# demeter_v22.net
KiCad netlist of a schematic drawn in EAGLE
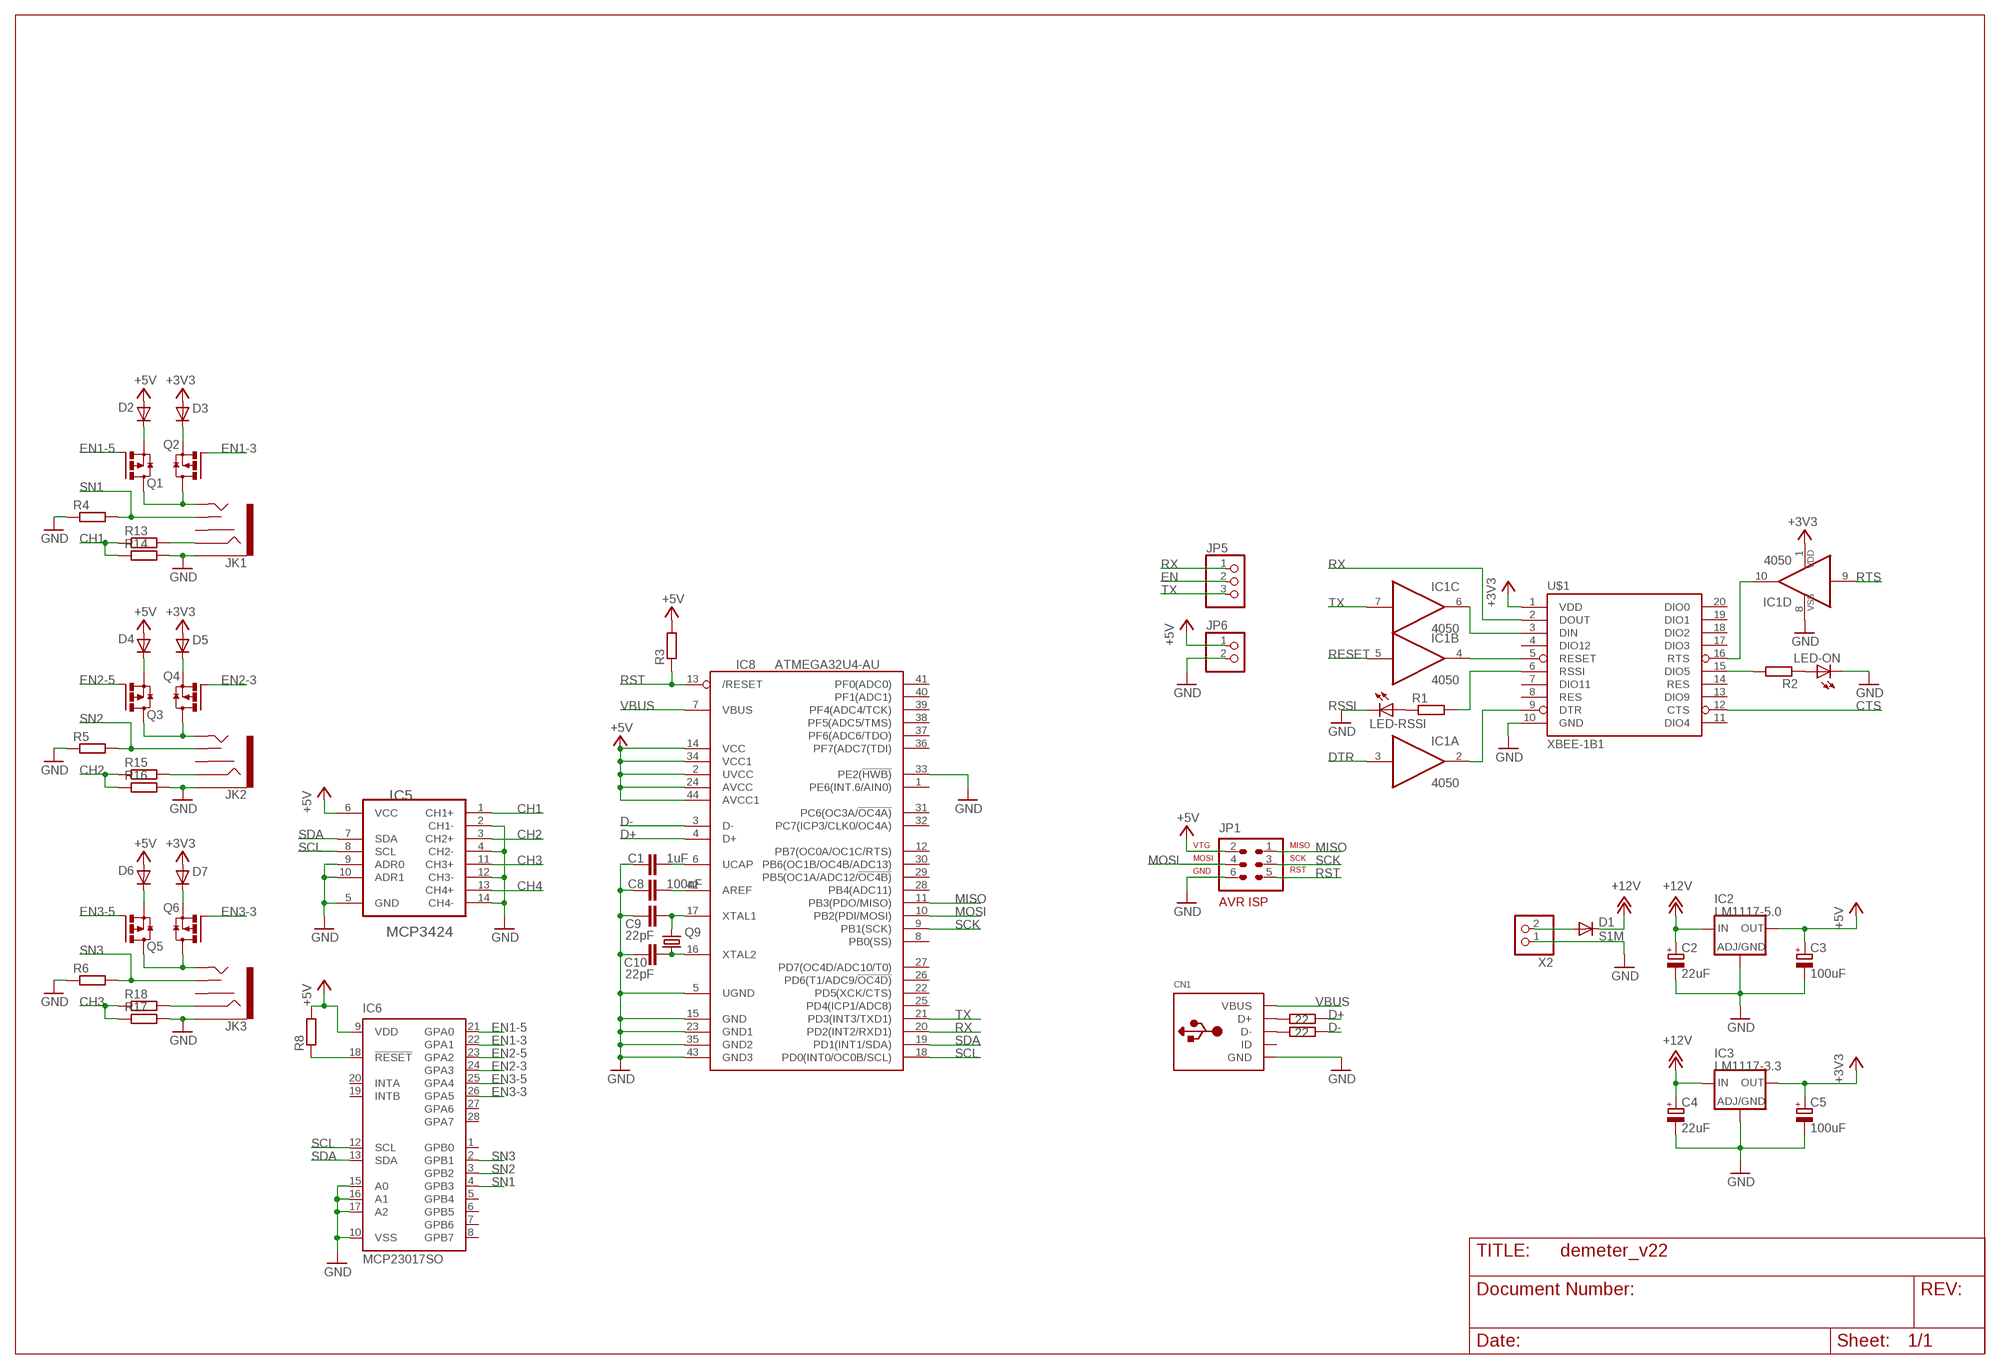
[diagram p0: schematic, sheet 1]

(export (version "E")
  (design (tool "Eeschema 10.0.6"))
  (components
    (comp (ref "C1")
      (value "1uF")
      (footprint "eagle-import:C0805K")
      (libsource (lib "eagle-import") (part "C-EUC0805K"))
    )
    (comp (ref "C2")
      (value "22uF")
      (footprint "eagle-import:PANASONIC_D")
      (libsource (lib "eagle-import") (part "CPOL-EUPD"))
    )
    (comp (ref "C3")
      (value "100uF")
      (footprint "eagle-import:PANASONIC_D")
      (libsource (lib "eagle-import") (part "CPOL-EUPD"))
    )
    (comp (ref "C4")
      (value "22uF")
      (footprint "eagle-import:PANASONIC_D")
      (libsource (lib "eagle-import") (part "CPOL-EUPD"))
    )
    (comp (ref "C5")
      (value "100uF")
      (footprint "eagle-import:PANASONIC_D")
      (libsource (lib "eagle-import") (part "CPOL-EUPD"))
    )
    (comp (ref "C8")
      (value "100nF")
      (footprint "eagle-import:C0805K")
      (libsource (lib "eagle-import") (part "C-EUC0805K"))
    )
    (comp (ref "C9")
      (value "22pF")
      (footprint "eagle-import:C0805K")
      (libsource (lib "eagle-import") (part "C-EUC0805K"))
    )
    (comp (ref "C10")
      (value "22pF")
      (footprint "eagle-import:C0805K")
      (libsource (lib "eagle-import") (part "C-EUC0805K"))
    )
    (comp (ref "CN1")
      (value "USBMINIB")
      (footprint "eagle-import:USB-MINIB")
      (libsource (lib "eagle-import") (part "USBMINIB"))
    )
    (comp (ref "D1")
      (value "S1M")
      (footprint "eagle-import:DO-214AC")
      (libsource (lib "eagle-import") (part "S1M"))
    )
    (comp (ref "D2")
      (value "MBR0520")
      (footprint "eagle-import:SOD123")
      (libsource (lib "eagle-import") (part "MBR0520"))
    )
    (comp (ref "D3")
      (value "MBR0520")
      (footprint "eagle-import:SOD123")
      (libsource (lib "eagle-import") (part "MBR0520"))
    )
    (comp (ref "D4")
      (value "MBR0520")
      (footprint "eagle-import:SOD123")
      (libsource (lib "eagle-import") (part "MBR0520"))
    )
    (comp (ref "D5")
      (value "MBR0520")
      (footprint "eagle-import:SOD123")
      (libsource (lib "eagle-import") (part "MBR0520"))
    )
    (comp (ref "D6")
      (value "MBR0520")
      (footprint "eagle-import:SOD123")
      (libsource (lib "eagle-import") (part "MBR0520"))
    )
    (comp (ref "D7")
      (value "MBR0520")
      (footprint "eagle-import:SOD123")
      (libsource (lib "eagle-import") (part "MBR0520"))
    )
    (comp (ref "IC1")
      (value "4050")
      (footprint "eagle-import:SO16")
      (libsource (lib "eagle-import") (part "4050D"))
    )
    (comp (ref "IC2")
      (value "LM1117-5.0")
      (footprint "eagle-import:DPACK")
      (libsource (lib "eagle-import") (part "LM1117DT"))
    )
    (comp (ref "IC3")
      (value "LM1117-3.3")
      (footprint "eagle-import:DPACK")
      (libsource (lib "eagle-import") (part "LM1117DT"))
    )
    (comp (ref "IC5")
      (value "MCP3424")
      (footprint "eagle-import:SO14")
      (fields (field (name "MPN") "MCP3424-E/SL"))
      (libsource (lib "eagle-import") (part "MCP3424"))
    )
    (comp (ref "IC6")
      (value "MCP23017SO")
      (footprint "eagle-import:SO28W")
      (fields (field (name "MF") "MICROCHIP") (field (name "MPN") "MCP23017-E/SO"))
      (libsource (lib "eagle-import") (part "MCP23017SO"))
    )
    (comp (ref "IC8")
      (value "ATMEGA32U4-AU")
      (footprint "eagle-import:TQFP44")
      (libsource (lib "eagle-import") (part "ATMEGA32U4-AU"))
    )
    (comp (ref "JK1")
      (value "AUDIO-JACK2PTH")
      (footprint "eagle-import:AUDIO-JACK")
      (libsource (lib "eagle-import") (part "AUDIO-JACK2PTH"))
    )
    (comp (ref "JK2")
      (value "AUDIO-JACK2PTH")
      (footprint "eagle-import:AUDIO-JACK")
      (libsource (lib "eagle-import") (part "AUDIO-JACK2PTH"))
    )
    (comp (ref "JK3")
      (value "AUDIO-JACK2PTH")
      (footprint "eagle-import:AUDIO-JACK")
      (libsource (lib "eagle-import") (part "AUDIO-JACK2PTH"))
    )
    (comp (ref "JP1")
      (value "AVR-ISP-6")
      (footprint "eagle-import:AVR-ISP-6")
      (libsource (lib "eagle-import") (part "AVR-ISP-6"))
    )
    (comp (ref "JP5")
      (value "PINHD-1X3180")
      (footprint "eagle-import:1X03")
      (libsource (lib "eagle-import") (part "PINHD-1X3180"))
    )
    (comp (ref "JP6")
      (value "PINHD-1X2")
      (footprint "eagle-import:1X02")
      (libsource (lib "eagle-import") (part "PINHD-1X2"))
    )
    (comp (ref "LED-ON")
      (value "LED0805")
      (footprint "eagle-import:CHIP-LED0805")
      (libsource (lib "eagle-import") (part "LED0805"))
    )
    (comp (ref "LED-RSSI")
      (value "LED0805")
      (footprint "eagle-import:CHIP-LED0805")
      (libsource (lib "eagle-import") (part "LED0805"))
    )
    (comp (ref "Q1")
      (value "IRLML6402")
      (footprint "eagle-import:SOT23")
      (libsource (lib "eagle-import") (part "IRLML6402"))
    )
    (comp (ref "Q2")
      (value "IRLML6402")
      (footprint "eagle-import:SOT23")
      (libsource (lib "eagle-import") (part "IRLML6402"))
    )
    (comp (ref "Q3")
      (value "IRLML6402")
      (footprint "eagle-import:SOT23")
      (libsource (lib "eagle-import") (part "IRLML6402"))
    )
    (comp (ref "Q4")
      (value "IRLML6402")
      (footprint "eagle-import:SOT23")
      (libsource (lib "eagle-import") (part "IRLML6402"))
    )
    (comp (ref "Q5")
      (value "IRLML6402")
      (footprint "eagle-import:SOT23")
      (libsource (lib "eagle-import") (part "IRLML6402"))
    )
    (comp (ref "Q6")
      (value "IRLML6402")
      (footprint "eagle-import:SOT23")
      (libsource (lib "eagle-import") (part "IRLML6402"))
    )
    (comp (ref "Q9")
      (value "CRYSTALHC49UP")
      (footprint "eagle-import:HC49UP")
      (libsource (lib "eagle-import") (part "CRYSTALHC49UP"))
    )
    (comp (ref "R1")
      (value "R-EU_R0805")
      (footprint "eagle-import:R0805")
      (libsource (lib "eagle-import") (part "R-EU_R0805"))
    )
    (comp (ref "R2")
      (value "R-EU_R0805")
      (footprint "eagle-import:R0805")
      (libsource (lib "eagle-import") (part "R-EU_R0805"))
    )
    (comp (ref "R3")
      (value "R-EU_R0805")
      (footprint "eagle-import:R0805")
      (libsource (lib "eagle-import") (part "R-EU_R0805"))
    )
    (comp (ref "R4")
      (value "R-EU_R0805")
      (footprint "eagle-import:R0805")
      (libsource (lib "eagle-import") (part "R-EU_R0805"))
    )
    (comp (ref "R5")
      (value "R-EU_R0805")
      (footprint "eagle-import:R0805")
      (libsource (lib "eagle-import") (part "R-EU_R0805"))
    )
    (comp (ref "R6")
      (value "R-EU_R0805")
      (footprint "eagle-import:R0805")
      (libsource (lib "eagle-import") (part "R-EU_R0805"))
    )
    (comp (ref "R8")
      (value "R-EU_R0805")
      (footprint "eagle-import:R0805")
      (libsource (lib "eagle-import") (part "R-EU_R0805"))
    )
    (comp (ref "R9")
      (value "22")
      (footprint "eagle-import:R0805")
      (libsource (lib "eagle-import") (part "R-EU_R0805"))
    )
    (comp (ref "R10")
      (value "22")
      (footprint "eagle-import:R0805")
      (libsource (lib "eagle-import") (part "R-EU_R0805"))
    )
    (comp (ref "R13")
      (value "R-EU_R0805")
      (footprint "eagle-import:R0805")
      (libsource (lib "eagle-import") (part "R-EU_R0805"))
    )
    (comp (ref "R14")
      (value "R-EU_R0805")
      (footprint "eagle-import:R0805")
      (libsource (lib "eagle-import") (part "R-EU_R0805"))
    )
    (comp (ref "R15")
      (value "R-EU_R0805")
      (footprint "eagle-import:R0805")
      (libsource (lib "eagle-import") (part "R-EU_R0805"))
    )
    (comp (ref "R16")
      (value "R-EU_R0805")
      (footprint "eagle-import:R0805")
      (libsource (lib "eagle-import") (part "R-EU_R0805"))
    )
    (comp (ref "R17")
      (value "R-EU_R0805")
      (footprint "eagle-import:R0805")
      (libsource (lib "eagle-import") (part "R-EU_R0805"))
    )
    (comp (ref "R18")
      (value "R-EU_R0805")
      (footprint "eagle-import:R0805")
      (libsource (lib "eagle-import") (part "R-EU_R0805"))
    )
    (comp (ref "U$1")
      (value "XBEE-1B1")
      (footprint "eagle-import:XBEE-1")
      (libsource (lib "eagle-import") (part "XBEE-1B1"))
    )
    (comp (ref "X2")
      (value "W237-102")
      (footprint "eagle-import:W237-102")
      (libsource (lib "eagle-import") (part "W237-102"))
    )
  )
  (nets
    (net (code "1") (name "+3V3") (class "Default")
      (node (ref "C5") (pin "+") (pinfunction "+_+") (pintype "passive"))
      (node (ref "D3") (pin "A") (pinfunction "A_A") (pintype "passive"))
      (node (ref "D5") (pin "A") (pinfunction "A_A") (pintype "passive"))
      (node (ref "D7") (pin "A") (pinfunction "A_A") (pintype "passive"))
      (node (ref "IC1") (pin "1") (pinfunction "VDD_1") (pintype "power_in"))
      (node (ref "IC3") (pin "4") (pinfunction "OUT_4") (pintype "passive"))
      (node (ref "U$1") (pin "1") (pinfunction "VDD_1") (pintype "power_in"))
    )
    (net (code "2") (name "+5V") (class "Default")
      (node (ref "C3") (pin "+") (pinfunction "+_+") (pintype "passive"))
      (node (ref "D2") (pin "A") (pinfunction "A_A") (pintype "passive"))
      (node (ref "D4") (pin "A") (pinfunction "A_A") (pintype "passive"))
      (node (ref "D6") (pin "A") (pinfunction "A_A") (pintype "passive"))
      (node (ref "IC2") (pin "4") (pinfunction "OUT_4") (pintype "passive"))
      (node (ref "IC5") (pin "6") (pinfunction "VCC_6") (pintype "power_in"))
      (node (ref "IC6") (pin "9") (pinfunction "VDD_9") (pintype "power_in"))
      (node (ref "IC8") (pin "14") (pinfunction "VCC_14") (pintype "bidirectional"))
      (node (ref "IC8") (pin "2") (pinfunction "UVCC_2") (pintype "bidirectional"))
      (node (ref "IC8") (pin "24") (pinfunction "AVCC_24") (pintype "bidirectional"))
      (node (ref "IC8") (pin "34") (pinfunction "VCC1_34") (pintype "bidirectional"))
      (node (ref "IC8") (pin "44") (pinfunction "AVCC1_44") (pintype "bidirectional"))
      (node (ref "JP1") (pin "2") (pinfunction "VTG_2") (pintype "passive"))
      (node (ref "JP6") (pin "1") (pinfunction "1_1") (pintype "passive"))
      (node (ref "R3") (pin "2") (pinfunction "2_2") (pintype "passive"))
      (node (ref "R8") (pin "2") (pinfunction "2_2") (pintype "passive"))
    )
    (net (code "3") (name "+12V") (class "Default")
      (node (ref "C2") (pin "+") (pinfunction "+_+") (pintype "passive"))
      (node (ref "C4") (pin "+") (pinfunction "+_+") (pintype "passive"))
      (node (ref "D1") (pin "C") (pinfunction "C_C") (pintype "passive"))
      (node (ref "IC2") (pin "3") (pinfunction "IN_3") (pintype "input"))
      (node (ref "IC3") (pin "3") (pinfunction "IN_3") (pintype "input"))
    )
    (net (code "4") (name "/CH1") (class "Default")
      (node (ref "IC5") (pin "1") (pinfunction "CH1+_1") (pintype "input"))
      (node (ref "R13") (pin "1") (pinfunction "1_1") (pintype "passive"))
      (node (ref "R14") (pin "1") (pinfunction "1_1") (pintype "passive"))
    )
    (net (code "5") (name "/CH2") (class "Default")
      (node (ref "IC5") (pin "3") (pinfunction "CH2+_3") (pintype "input"))
      (node (ref "R15") (pin "1") (pinfunction "1_1") (pintype "passive"))
      (node (ref "R16") (pin "1") (pinfunction "1_1") (pintype "passive"))
    )
    (net (code "6") (name "/CH3") (class "Default")
      (node (ref "IC5") (pin "11") (pinfunction "CH3+_11") (pintype "input"))
      (node (ref "R17") (pin "1") (pinfunction "1_1") (pintype "passive"))
      (node (ref "R18") (pin "1") (pinfunction "1_1") (pintype "passive"))
    )
    (net (code "7") (name "/CH4") (class "Default")
      (node (ref "IC5") (pin "13") (pinfunction "CH4+_13") (pintype "input"))
    )
    (net (code "8") (name "/CTS") (class "Default")
      (node (ref "U$1") (pin "12") (pinfunction "CTS_12") (pintype "output"))
    )
    (net (code "9") (name "/D+") (class "Default")
      (node (ref "IC8") (pin "4") (pinfunction "D+_4") (pintype "bidirectional"))
      (node (ref "R9") (pin "1") (pinfunction "1_1") (pintype "passive"))
    )
    (net (code "10") (name "/D-") (class "Default")
      (node (ref "IC8") (pin "3") (pinfunction "D-_3") (pintype "bidirectional"))
      (node (ref "R10") (pin "1") (pinfunction "1_1") (pintype "passive"))
    )
    (net (code "11") (name "/DTR") (class "Default")
      (node (ref "IC1") (pin "3") (pinfunction "I_3") (pintype "input"))
    )
    (net (code "12") (name "/EN") (class "Default")
      (node (ref "JP5") (pin "2") (pinfunction "2_2") (pintype "passive"))
    )
    (net (code "13") (name "/EN1-3") (class "Default")
      (node (ref "IC6") (pin "22") (pinfunction "GPA1_22") (pintype "bidirectional"))
      (node (ref "Q2") (pin "1") (pinfunction "G_1") (pintype "passive"))
    )
    (net (code "14") (name "/EN1-5") (class "Default")
      (node (ref "IC6") (pin "21") (pinfunction "GPA0_21") (pintype "bidirectional"))
      (node (ref "Q1") (pin "1") (pinfunction "G_1") (pintype "passive"))
    )
    (net (code "15") (name "/EN2-3") (class "Default")
      (node (ref "IC6") (pin "24") (pinfunction "GPA3_24") (pintype "bidirectional"))
      (node (ref "Q4") (pin "1") (pinfunction "G_1") (pintype "passive"))
    )
    (net (code "16") (name "/EN2-5") (class "Default")
      (node (ref "IC6") (pin "23") (pinfunction "GPA2_23") (pintype "bidirectional"))
      (node (ref "Q3") (pin "1") (pinfunction "G_1") (pintype "passive"))
    )
    (net (code "17") (name "/EN3-3") (class "Default")
      (node (ref "IC6") (pin "26") (pinfunction "GPA5_26") (pintype "bidirectional"))
      (node (ref "Q6") (pin "1") (pinfunction "G_1") (pintype "passive"))
    )
    (net (code "18") (name "/EN3-5") (class "Default")
      (node (ref "IC6") (pin "25") (pinfunction "GPA4_25") (pintype "bidirectional"))
      (node (ref "Q5") (pin "1") (pinfunction "G_1") (pintype "passive"))
    )
    (net (code "19") (name "/MISO") (class "Default")
      (node (ref "IC8") (pin "11") (pinfunction "PB3(PDO/MISO)_11") (pintype "bidirectional"))
      (node (ref "JP1") (pin "1") (pinfunction "MISO_1") (pintype "passive"))
    )
    (net (code "20") (name "/MOSI") (class "Default")
      (node (ref "IC8") (pin "10") (pinfunction "PB2(PDI/MOSI)_10") (pintype "bidirectional"))
      (node (ref "JP1") (pin "4") (pinfunction "MOSI_4") (pintype "passive"))
    )
    (net (code "21") (name "/RESET") (class "Default")
      (node (ref "IC1") (pin "5") (pinfunction "I_5") (pintype "input"))
    )
    (net (code "22") (name "/RSSI") (class "Default")
      (node (ref "R1") (pin "2") (pinfunction "2_2") (pintype "passive"))
      (node (ref "U$1") (pin "6") (pinfunction "RSSI_6") (pintype "bidirectional"))
    )
    (net (code "23") (name "/RST") (class "Default")
      (node (ref "IC8") (pin "13") (pinfunction "/RESET_13") (pintype "bidirectional"))
      (node (ref "JP1") (pin "5") (pinfunction "RST_5") (pintype "passive"))
      (node (ref "R3") (pin "1") (pinfunction "1_1") (pintype "passive"))
    )
    (net (code "24") (name "/RTS") (class "Default")
      (node (ref "IC1") (pin "9") (pinfunction "I_9") (pintype "input"))
    )
    (net (code "25") (name "/RX") (class "Default")
      (node (ref "IC8") (pin "20") (pinfunction "PD2(INT2/RXD1)_20") (pintype "bidirectional"))
      (node (ref "JP5") (pin "1") (pinfunction "1_1") (pintype "passive"))
      (node (ref "U$1") (pin "2") (pinfunction "DOUT_2") (pintype "output"))
    )
    (net (code "26") (name "/SCK") (class "Default")
      (node (ref "IC8") (pin "9") (pinfunction "PB1(SCK)_9") (pintype "bidirectional"))
      (node (ref "JP1") (pin "3") (pinfunction "SCK_3") (pintype "passive"))
    )
    (net (code "27") (name "/SCL") (class "Default")
      (node (ref "IC5") (pin "8") (pinfunction "SCL_8") (pintype "input"))
      (node (ref "IC6") (pin "12") (pinfunction "SCL_12") (pintype "input"))
      (node (ref "IC8") (pin "18") (pinfunction "PD0(INT0/OC0B/SCL)_18") (pintype "bidirectional"))
    )
    (net (code "28") (name "/SDA") (class "Default")
      (node (ref "IC5") (pin "7") (pinfunction "SDA_7") (pintype "bidirectional"))
      (node (ref "IC6") (pin "13") (pinfunction "SDA_13") (pintype "bidirectional"))
      (node (ref "IC8") (pin "19") (pinfunction "PD1(INT1/SDA)_19") (pintype "bidirectional"))
    )
    (net (code "29") (name "/SN1") (class "Default")
      (node (ref "IC6") (pin "4") (pinfunction "GPB3_4") (pintype "bidirectional"))
      (node (ref "JK1") (pin "TSH") (pinfunction "TSH_TSH") (pintype "bidirectional"))
      (node (ref "R4") (pin "2") (pinfunction "2_2") (pintype "passive"))
    )
    (net (code "30") (name "/SN2") (class "Default")
      (node (ref "IC6") (pin "3") (pinfunction "GPB2_3") (pintype "bidirectional"))
      (node (ref "JK2") (pin "TSH") (pinfunction "TSH_TSH") (pintype "bidirectional"))
      (node (ref "R5") (pin "2") (pinfunction "2_2") (pintype "passive"))
    )
    (net (code "31") (name "/SN3") (class "Default")
      (node (ref "IC6") (pin "2") (pinfunction "GPB1_2") (pintype "bidirectional"))
      (node (ref "JK3") (pin "TSH") (pinfunction "TSH_TSH") (pintype "bidirectional"))
      (node (ref "R6") (pin "2") (pinfunction "2_2") (pintype "passive"))
    )
    (net (code "32") (name "/TX") (class "Default")
      (node (ref "IC1") (pin "7") (pinfunction "I_7") (pintype "input"))
      (node (ref "IC8") (pin "21") (pinfunction "PD3(INT3/TXD1)_21") (pintype "bidirectional"))
      (node (ref "JP5") (pin "3") (pinfunction "3_3") (pintype "passive"))
    )
    (net (code "33") (name "/VBUS") (class "Default")
      (node (ref "CN1") (pin "VBUS") (pinfunction "VBUS_VBUS") (pintype "power_in"))
      (node (ref "IC8") (pin "7") (pinfunction "VBUS_7") (pintype "bidirectional"))
    )
    (net (code "34") (name "GND") (class "Default")
      (node (ref "C1") (pin "2") (pinfunction "2_2") (pintype "passive"))
      (node (ref "C10") (pin "2") (pinfunction "2_2") (pintype "passive"))
      (node (ref "C2") (pin "-") (pinfunction "-_-") (pintype "passive"))
      (node (ref "C3") (pin "-") (pinfunction "-_-") (pintype "passive"))
      (node (ref "C4") (pin "-") (pinfunction "-_-") (pintype "passive"))
      (node (ref "C5") (pin "-") (pinfunction "-_-") (pintype "passive"))
      (node (ref "C8") (pin "2") (pinfunction "2_2") (pintype "passive"))
      (node (ref "C9") (pin "2") (pinfunction "2_2") (pintype "passive"))
      (node (ref "CN1") (pin "GND") (pinfunction "GND_GND") (pintype "power_in"))
      (node (ref "IC1") (pin "8") (pinfunction "VSS_8") (pintype "power_in"))
      (node (ref "IC2") (pin "1") (pinfunction "ADJ_1") (pintype "input"))
      (node (ref "IC3") (pin "1") (pinfunction "ADJ_1") (pintype "input"))
      (node (ref "IC5") (pin "10") (pinfunction "ADR1_10") (pintype "input"))
      (node (ref "IC5") (pin "12") (pinfunction "CH3-_12") (pintype "input"))
      (node (ref "IC5") (pin "14") (pinfunction "CH4-_14") (pintype "input"))
      (node (ref "IC5") (pin "2") (pinfunction "CH1-_2") (pintype "input"))
      (node (ref "IC5") (pin "4") (pinfunction "CH2-_4") (pintype "input"))
      (node (ref "IC5") (pin "5") (pinfunction "GND_5") (pintype "power_in"))
      (node (ref "IC5") (pin "9") (pinfunction "ADR0_9") (pintype "input"))
      (node (ref "IC6") (pin "10") (pinfunction "VSS_10") (pintype "power_in"))
      (node (ref "IC6") (pin "15") (pinfunction "A0_15") (pintype "input"))
      (node (ref "IC6") (pin "16") (pinfunction "A1_16") (pintype "input"))
      (node (ref "IC6") (pin "17") (pinfunction "A2_17") (pintype "input"))
      (node (ref "IC8") (pin "15") (pinfunction "GND_15") (pintype "bidirectional"))
      (node (ref "IC8") (pin "23") (pinfunction "GND1_23") (pintype "bidirectional"))
      (node (ref "IC8") (pin "33") (pinfunction "PE2(~{HWB})_33") (pintype "bidirectional"))
      (node (ref "IC8") (pin "35") (pinfunction "GND2_35") (pintype "bidirectional"))
      (node (ref "IC8") (pin "43") (pinfunction "GND3_43") (pintype "bidirectional"))
      (node (ref "IC8") (pin "5") (pinfunction "UGND_5") (pintype "bidirectional"))
      (node (ref "JK1") (pin "SLEEVE") (pinfunction "SLEEVE_SLEEVE") (pintype "bidirectional"))
      (node (ref "JK2") (pin "SLEEVE") (pinfunction "SLEEVE_SLEEVE") (pintype "bidirectional"))
      (node (ref "JK3") (pin "SLEEVE") (pinfunction "SLEEVE_SLEEVE") (pintype "bidirectional"))
      (node (ref "JP1") (pin "6") (pinfunction "GND_6") (pintype "passive"))
      (node (ref "JP6") (pin "2") (pinfunction "2_2") (pintype "passive"))
      (node (ref "LED-ON") (pin "C") (pinfunction "C_C") (pintype "passive"))
      (node (ref "LED-RSSI") (pin "C") (pinfunction "C_C") (pintype "passive"))
      (node (ref "R14") (pin "2") (pinfunction "2_2") (pintype "passive"))
      (node (ref "R16") (pin "2") (pinfunction "2_2") (pintype "passive"))
      (node (ref "R17") (pin "2") (pinfunction "2_2") (pintype "passive"))
      (node (ref "R4") (pin "1") (pinfunction "1_1") (pintype "passive"))
      (node (ref "R5") (pin "1") (pinfunction "1_1") (pintype "passive"))
      (node (ref "R6") (pin "1") (pinfunction "1_1") (pintype "passive"))
      (node (ref "U$1") (pin "10") (pinfunction "GND_10") (pintype "power_in"))
      (node (ref "X2") (pin "1") (pinfunction "1_1") (pintype "passive"))
    )
    (net (code "35") (name "Net-(CN1-PadD+)") (class "Default")
      (node (ref "CN1") (pin "D+") (pinfunction "D+_D+") (pintype "bidirectional"))
      (node (ref "R9") (pin "2") (pinfunction "2_2") (pintype "passive"))
    )
    (net (code "36") (name "Net-(CN1-PadD-)") (class "Default")
      (node (ref "CN1") (pin "D-") (pinfunction "D-_D-") (pintype "bidirectional"))
      (node (ref "R10") (pin "2") (pinfunction "2_2") (pintype "passive"))
    )
    (net (code "37") (name "Net-(D1-PadA)") (class "Default")
      (node (ref "D1") (pin "A") (pinfunction "A_A") (pintype "passive"))
      (node (ref "X2") (pin "2") (pinfunction "2_2") (pintype "passive"))
    )
    (net (code "38") (name "Net-(IC1A-O)") (class "Default")
      (node (ref "IC1") (pin "2") (pinfunction "O_2") (pintype "output"))
      (node (ref "U$1") (pin "9") (pinfunction "DTR_9") (pintype "bidirectional"))
    )
    (net (code "39") (name "Net-(IC1B-O)") (class "Default")
      (node (ref "IC1") (pin "4") (pinfunction "O_4") (pintype "output"))
      (node (ref "U$1") (pin "5") (pinfunction "RESET_5") (pintype "input"))
    )
    (net (code "40") (name "Net-(IC1C-O)") (class "Default")
      (node (ref "IC1") (pin "6") (pinfunction "O_6") (pintype "output"))
      (node (ref "U$1") (pin "3") (pinfunction "DIN_3") (pintype "input"))
    )
    (net (code "41") (name "Net-(IC1D-O)") (class "Default")
      (node (ref "IC1") (pin "10") (pinfunction "O_10") (pintype "output"))
      (node (ref "U$1") (pin "16") (pinfunction "RTS_16") (pintype "input"))
    )
    (net (code "42") (name "Net-(IC6-~{RESET})") (class "Default")
      (node (ref "IC6") (pin "18") (pinfunction "~{RESET}_18") (pintype "input"))
      (node (ref "R8") (pin "1") (pinfunction "1_1") (pintype "passive"))
    )
    (net (code "43") (name "Net-(IC8-AREF)") (class "Default")
      (node (ref "C8") (pin "1") (pinfunction "1_1") (pintype "passive"))
      (node (ref "IC8") (pin "42") (pinfunction "AREF_42") (pintype "bidirectional"))
    )
    (net (code "44") (name "Net-(IC8-UCAP)") (class "Default")
      (node (ref "C1") (pin "1") (pinfunction "1_1") (pintype "passive"))
      (node (ref "IC8") (pin "6") (pinfunction "UCAP_6") (pintype "bidirectional"))
    )
    (net (code "45") (name "Net-(IC8-XTAL1)") (class "Default")
      (node (ref "C9") (pin "1") (pinfunction "1_1") (pintype "passive"))
      (node (ref "IC8") (pin "17") (pinfunction "XTAL1_17") (pintype "bidirectional"))
      (node (ref "Q9") (pin "2") (pinfunction "2_2") (pintype "passive"))
    )
    (net (code "46") (name "Net-(IC8-XTAL2)") (class "Default")
      (node (ref "C10") (pin "1") (pinfunction "1_1") (pintype "passive"))
      (node (ref "IC8") (pin "16") (pinfunction "XTAL2_16") (pintype "bidirectional"))
      (node (ref "Q9") (pin "1") (pinfunction "1_1") (pintype "passive"))
    )
    (net (code "47") (name "Net-(JK1-PadRING)") (class "Default")
      (node (ref "JK1") (pin "RING") (pinfunction "RING_RING") (pintype "bidirectional"))
      (node (ref "R13") (pin "2") (pinfunction "2_2") (pintype "passive"))
    )
    (net (code "48") (name "Net-(JK2-PadRING)") (class "Default")
      (node (ref "JK2") (pin "RING") (pinfunction "RING_RING") (pintype "bidirectional"))
      (node (ref "R15") (pin "2") (pinfunction "2_2") (pintype "passive"))
    )
    (net (code "49") (name "Net-(JK3-PadRING)") (class "Default")
      (node (ref "JK3") (pin "RING") (pinfunction "RING_RING") (pintype "bidirectional"))
      (node (ref "R18") (pin "2") (pinfunction "2_2") (pintype "passive"))
    )
    (net (code "50") (name "Net-(LED-ON-PadA)") (class "Default")
      (node (ref "LED-ON") (pin "A") (pinfunction "A_A") (pintype "passive"))
      (node (ref "R2") (pin "1") (pinfunction "1_1") (pintype "passive"))
    )
    (net (code "51") (name "Net-(LED-RSSI-PadA)") (class "Default")
      (node (ref "LED-RSSI") (pin "A") (pinfunction "A_A") (pintype "passive"))
      (node (ref "R1") (pin "1") (pinfunction "1_1") (pintype "passive"))
    )
    (net (code "52") (name "Net-(Q1-D)") (class "Default")
      (node (ref "JK1") (pin "TIP") (pinfunction "TIP_TIP") (pintype "bidirectional"))
      (node (ref "Q1") (pin "3") (pinfunction "D_3") (pintype "passive"))
      (node (ref "Q2") (pin "3") (pinfunction "D_3") (pintype "passive"))
    )
    (net (code "53") (name "Net-(Q1-S)") (class "Default")
      (node (ref "D2") (pin "C") (pinfunction "C_C") (pintype "passive"))
      (node (ref "Q1") (pin "2") (pinfunction "S_2") (pintype "passive"))
    )
    (net (code "54") (name "Net-(Q2-S)") (class "Default")
      (node (ref "D3") (pin "C") (pinfunction "C_C") (pintype "passive"))
      (node (ref "Q2") (pin "2") (pinfunction "S_2") (pintype "passive"))
    )
    (net (code "55") (name "Net-(Q3-D)") (class "Default")
      (node (ref "JK2") (pin "TIP") (pinfunction "TIP_TIP") (pintype "bidirectional"))
      (node (ref "Q3") (pin "3") (pinfunction "D_3") (pintype "passive"))
      (node (ref "Q4") (pin "3") (pinfunction "D_3") (pintype "passive"))
    )
    (net (code "56") (name "Net-(Q3-S)") (class "Default")
      (node (ref "D4") (pin "C") (pinfunction "C_C") (pintype "passive"))
      (node (ref "Q3") (pin "2") (pinfunction "S_2") (pintype "passive"))
    )
    (net (code "57") (name "Net-(Q4-S)") (class "Default")
      (node (ref "D5") (pin "C") (pinfunction "C_C") (pintype "passive"))
      (node (ref "Q4") (pin "2") (pinfunction "S_2") (pintype "passive"))
    )
    (net (code "58") (name "Net-(Q5-D)") (class "Default")
      (node (ref "JK3") (pin "TIP") (pinfunction "TIP_TIP") (pintype "bidirectional"))
      (node (ref "Q5") (pin "3") (pinfunction "D_3") (pintype "passive"))
      (node (ref "Q6") (pin "3") (pinfunction "D_3") (pintype "passive"))
    )
    (net (code "59") (name "Net-(Q5-S)") (class "Default")
      (node (ref "D6") (pin "C") (pinfunction "C_C") (pintype "passive"))
      (node (ref "Q5") (pin "2") (pinfunction "S_2") (pintype "passive"))
    )
    (net (code "60") (name "Net-(Q6-S)") (class "Default")
      (node (ref "D7") (pin "C") (pinfunction "C_C") (pintype "passive"))
      (node (ref "Q6") (pin "2") (pinfunction "S_2") (pintype "passive"))
    )
    (net (code "61") (name "Net-(U$1-DIO5)") (class "Default")
      (node (ref "R2") (pin "2") (pinfunction "2_2") (pintype "passive"))
      (node (ref "U$1") (pin "15") (pinfunction "DIO5_15") (pintype "bidirectional"))
    )
    (net (code "62") (name "unconnected-(CN1-PadID)") (class "Default")
      (node (ref "CN1") (pin "ID") (pinfunction "ID_ID") (pintype "bidirectional"))
    )
    (net (code "63") (name "unconnected-(IC6-GPA6-Pad27)") (class "Default")
      (node (ref "IC6") (pin "27") (pinfunction "GPA6_27") (pintype "bidirectional"))
    )
    (net (code "64") (name "unconnected-(IC6-GPA7-Pad28)") (class "Default")
      (node (ref "IC6") (pin "28") (pinfunction "GPA7_28") (pintype "bidirectional"))
    )
    (net (code "65") (name "unconnected-(IC6-GPB0-Pad1)") (class "Default")
      (node (ref "IC6") (pin "1") (pinfunction "GPB0_1") (pintype "bidirectional"))
    )
    (net (code "66") (name "unconnected-(IC6-GPB4-Pad5)") (class "Default")
      (node (ref "IC6") (pin "5") (pinfunction "GPB4_5") (pintype "bidirectional"))
    )
    (net (code "67") (name "unconnected-(IC6-GPB5-Pad6)") (class "Default")
      (node (ref "IC6") (pin "6") (pinfunction "GPB5_6") (pintype "bidirectional"))
    )
    (net (code "68") (name "unconnected-(IC6-GPB6-Pad7)") (class "Default")
      (node (ref "IC6") (pin "7") (pinfunction "GPB6_7") (pintype "bidirectional"))
    )
    (net (code "69") (name "unconnected-(IC6-GPB7-Pad8)") (class "Default")
      (node (ref "IC6") (pin "8") (pinfunction "GPB7_8") (pintype "bidirectional"))
    )
    (net (code "70") (name "unconnected-(IC6-INTA-Pad20)") (class "Default")
      (node (ref "IC6") (pin "20") (pinfunction "INTA_20") (pintype "output"))
    )
    (net (code "71") (name "unconnected-(IC6-INTB-Pad19)") (class "Default")
      (node (ref "IC6") (pin "19") (pinfunction "INTB_19") (pintype "output"))
    )
    (net (code "72") (name "unconnected-(IC8-PB0(SS)-Pad8)") (class "Default")
      (node (ref "IC8") (pin "8") (pinfunction "PB0(SS)_8") (pintype "bidirectional"))
    )
    (net (code "73") (name "unconnected-(IC8-PB4(ADC11)-Pad28)") (class "Default")
      (node (ref "IC8") (pin "28") (pinfunction "PB4(ADC11)_28") (pintype "bidirectional"))
    )
    (net (code "74") (name "unconnected-(IC8-PB5(OC1A{slash}ADC12{slash}~{OC4B})-Pad29)") (class "Default")
      (node (ref "IC8") (pin "29") (pinfunction "PB5(OC1A/ADC12/~{OC4B})_29") (pintype "bidirectional"))
    )
    (net (code "75") (name "unconnected-(IC8-PB6(OC1B{slash}OC4B{slash}ADC13)-Pad30)") (class "Default")
      (node (ref "IC8") (pin "30") (pinfunction "PB6(OC1B/OC4B/ADC13)_30") (pintype "bidirectional"))
    )
    (net (code "76") (name "unconnected-(IC8-PB7(OC0A{slash}OC1C{slash}RTS)-Pad12)") (class "Default")
      (node (ref "IC8") (pin "12") (pinfunction "PB7(OC0A/OC1C/RTS)_12") (pintype "bidirectional"))
    )
    (net (code "77") (name "unconnected-(IC8-PC6(OC3A{slash}~{OC4A})-Pad31)") (class "Default")
      (node (ref "IC8") (pin "31") (pinfunction "PC6(OC3A/~{OC4A})_31") (pintype "bidirectional"))
    )
    (net (code "78") (name "unconnected-(IC8-PC7(ICP3{slash}CLK0{slash}OC4A)-Pad32)") (class "Default")
      (node (ref "IC8") (pin "32") (pinfunction "PC7(ICP3/CLK0/OC4A)_32") (pintype "bidirectional"))
    )
    (net (code "79") (name "unconnected-(IC8-PD4(ICP1{slash}ADC8)-Pad25)") (class "Default")
      (node (ref "IC8") (pin "25") (pinfunction "PD4(ICP1/ADC8)_25") (pintype "bidirectional"))
    )
    (net (code "80") (name "unconnected-(IC8-PD5(XCK{slash}CTS)-Pad22)") (class "Default")
      (node (ref "IC8") (pin "22") (pinfunction "PD5(XCK/CTS)_22") (pintype "bidirectional"))
    )
    (net (code "81") (name "unconnected-(IC8-PD6(T1{slash}ADC9{slash}~{OC4D})-Pad26)") (class "Default")
      (node (ref "IC8") (pin "26") (pinfunction "PD6(T1/ADC9/~{OC4D})_26") (pintype "bidirectional"))
    )
    (net (code "82") (name "unconnected-(IC8-PD7(OC4D{slash}ADC10{slash}T0)-Pad27)") (class "Default")
      (node (ref "IC8") (pin "27") (pinfunction "PD7(OC4D/ADC10/T0)_27") (pintype "bidirectional"))
    )
    (net (code "83") (name "unconnected-(IC8-PE6(INT.6{slash}AIN0)-Pad1)") (class "Default")
      (node (ref "IC8") (pin "1") (pinfunction "PE6(INT.6/AIN0)_1") (pintype "bidirectional"))
    )
    (net (code "84") (name "unconnected-(IC8-PF0(ADC0)-Pad41)") (class "Default")
      (node (ref "IC8") (pin "41") (pinfunction "PF0(ADC0)_41") (pintype "bidirectional"))
    )
    (net (code "85") (name "unconnected-(IC8-PF1(ADC1)-Pad40)") (class "Default")
      (node (ref "IC8") (pin "40") (pinfunction "PF1(ADC1)_40") (pintype "bidirectional"))
    )
    (net (code "86") (name "unconnected-(IC8-PF4(ADC4{slash}TCK)-Pad39)") (class "Default")
      (node (ref "IC8") (pin "39") (pinfunction "PF4(ADC4/TCK)_39") (pintype "bidirectional"))
    )
    (net (code "87") (name "unconnected-(IC8-PF5(ADC5{slash}TMS)-Pad38)") (class "Default")
      (node (ref "IC8") (pin "38") (pinfunction "PF5(ADC5/TMS)_38") (pintype "bidirectional"))
    )
    (net (code "88") (name "unconnected-(IC8-PF6(ADC6{slash}TDO)-Pad37)") (class "Default")
      (node (ref "IC8") (pin "37") (pinfunction "PF6(ADC6/TDO)_37") (pintype "bidirectional"))
    )
    (net (code "89") (name "unconnected-(IC8-PF7(ADC7(TDI)-Pad36)") (class "Default")
      (node (ref "IC8") (pin "36") (pinfunction "PF7(ADC7(TDI)_36") (pintype "bidirectional"))
    )
    (net (code "90") (name "unconnected-(JK1-PadRSH)") (class "Default")
      (node (ref "JK1") (pin "RSH") (pinfunction "RSH_RSH") (pintype "bidirectional"))
    )
    (net (code "91") (name "unconnected-(JK2-PadRSH)") (class "Default")
      (node (ref "JK2") (pin "RSH") (pinfunction "RSH_RSH") (pintype "bidirectional"))
    )
    (net (code "92") (name "unconnected-(JK3-PadRSH)") (class "Default")
      (node (ref "JK3") (pin "RSH") (pinfunction "RSH_RSH") (pintype "bidirectional"))
    )
    (net (code "93") (name "unconnected-(U$1-DIO0-Pad20)") (class "Default")
      (node (ref "U$1") (pin "20") (pinfunction "DIO0_20") (pintype "bidirectional"))
    )
    (net (code "94") (name "unconnected-(U$1-DIO1-Pad19)") (class "Default")
      (node (ref "U$1") (pin "19") (pinfunction "DIO1_19") (pintype "bidirectional"))
    )
    (net (code "95") (name "unconnected-(U$1-DIO2-Pad18)") (class "Default")
      (node (ref "U$1") (pin "18") (pinfunction "DIO2_18") (pintype "bidirectional"))
    )
    (net (code "96") (name "unconnected-(U$1-DIO3-Pad17)") (class "Default")
      (node (ref "U$1") (pin "17") (pinfunction "DIO3_17") (pintype "bidirectional"))
    )
    (net (code "97") (name "unconnected-(U$1-DIO4-Pad11)") (class "Default")
      (node (ref "U$1") (pin "11") (pinfunction "DIO4_11") (pintype "bidirectional"))
    )
    (net (code "98") (name "unconnected-(U$1-DIO9-Pad13)") (class "Default")
      (node (ref "U$1") (pin "13") (pinfunction "DIO9_13") (pintype "bidirectional"))
    )
    (net (code "99") (name "unconnected-(U$1-DIO11-Pad7)") (class "Default")
      (node (ref "U$1") (pin "7") (pinfunction "DIO11_7") (pintype "bidirectional"))
    )
    (net (code "100") (name "unconnected-(U$1-DIO12-Pad4)") (class "Default")
      (node (ref "U$1") (pin "4") (pinfunction "DIO12_4") (pintype "bidirectional"))
    )
    (net (code "101") (name "unconnected-(U$1-RES-Pad8)") (class "Default")
      (node (ref "U$1") (pin "8") (pinfunction "RES_8") (pintype "bidirectional"))
    )
    (net (code "102") (name "unconnected-(U$1-RES-Pad14)") (class "Default")
      (node (ref "U$1") (pin "14") (pinfunction "RES_14") (pintype "bidirectional"))
    )
  )
)
